# 08-_MCU_PORTE_F_G.net
KiCad netlist of a schematic drawn in Altium Designer
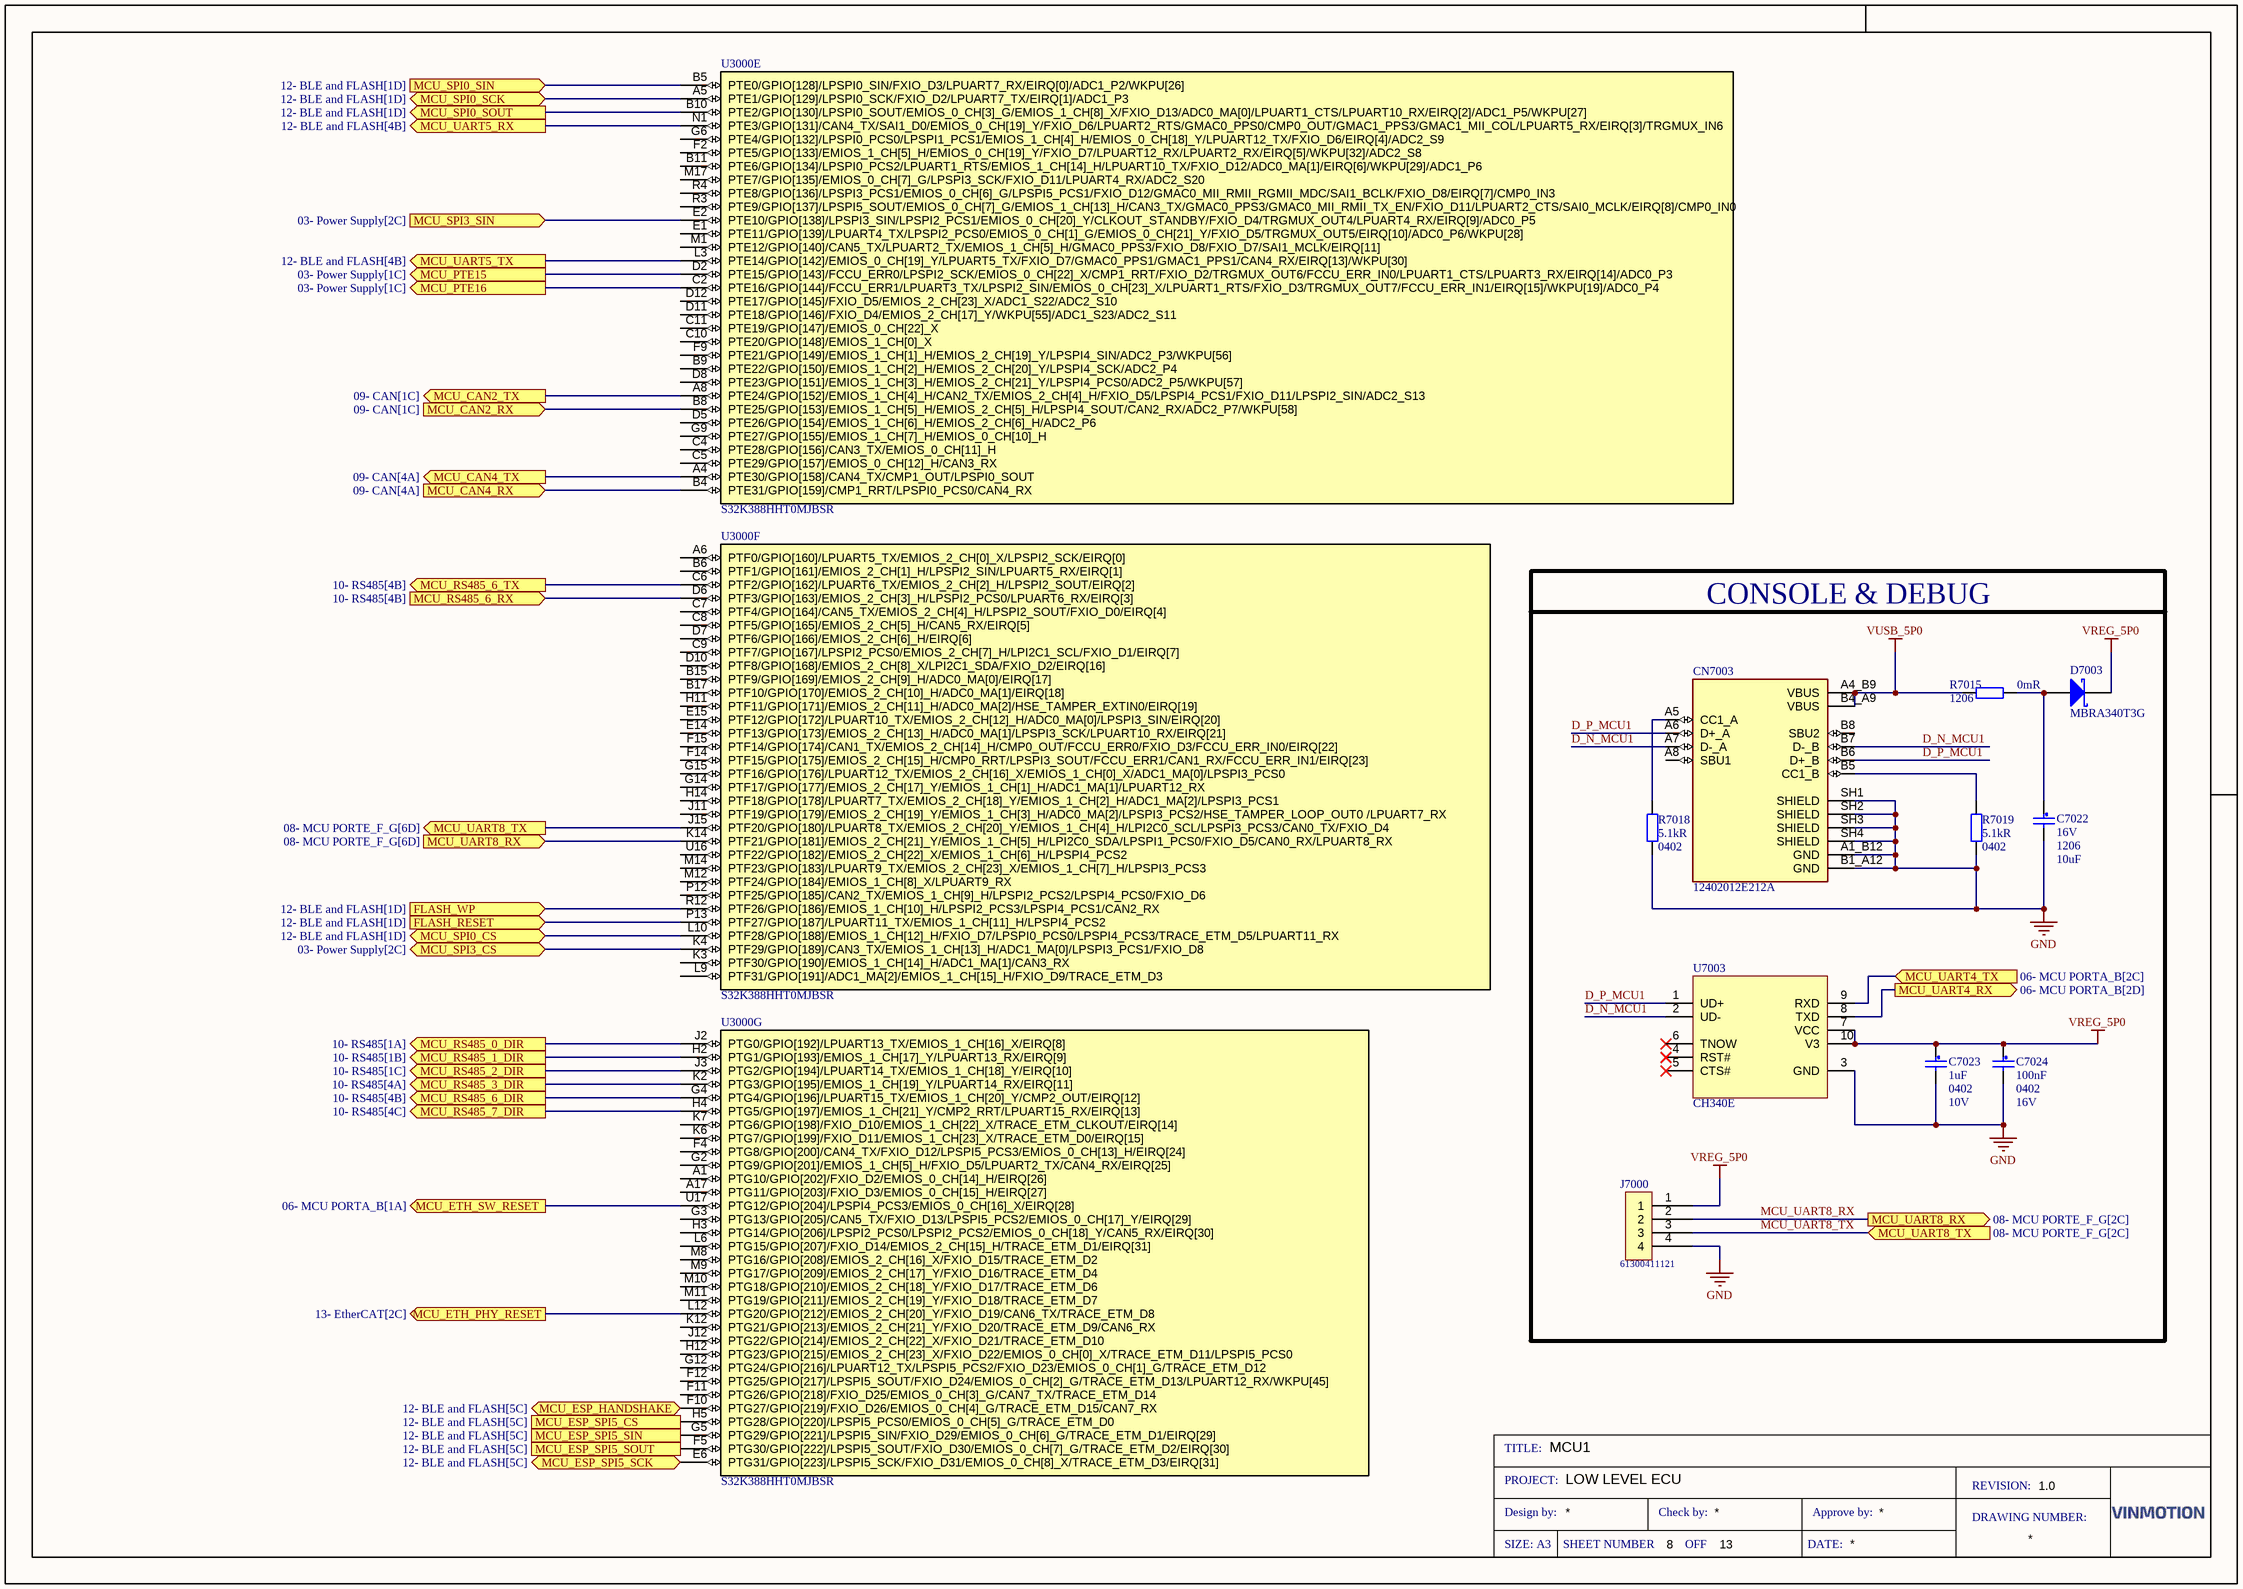
[diagram p0: 08- MCU PORTE_F_G.SchDoc]

(export (version "E")
  (design (tool "Eeschema 10.0.6"))
  (components
    (comp (ref "C7022")
      (value "CL31B106KOHVPNE")
      (footprint "CAP1206")
      (description "CAP CER 10uF 16V 10% X7R 1206 SMD")
      (fields
        (field (name "TOLERANCE") "10%")
        (field (name "VOLTAGE RATING") "16V")
        (field (name "CASE/PACKAGE") "1206")
        (field (name "CAPACITANCE") "10uF")
      )
      (libsource (lib "VMO_Lib") (part "CMP-00045-5"))
    )
    (comp (ref "C7023")
      (value "1uF")
      (footprint "CAP0402")
      (description "CAP CER 1UF 10V X6S 0402")
      (fields
        (field (name "MANUFACTURER") "Samsung")
        (field (name "MANUFACTURER PART NUMBER") "CL05X105KP5NNNC")
        (field (name "CASE/PACKAGE") "0402")
        (field (name "RATED DC VOLTAGE (URDC)") "10V")
      )
      (libsource (lib "VMO_Lib") (part "CMP-01106-1"))
    )
    (comp (ref "C7024")
      (value "0402YC104KAT2A")
      (footprint "CAP0402")
      (description "CAP CER 0.1UF 16V X7R 0402")
      (fields
        (field (name "CAPACITANCE") "100nF")
        (field (name "CASE/PACKAGE") "0402")
        (field (name "VOLTAGE RATING (DC)") "16V")
      )
      (libsource (lib "VMO_Lib") (part "CMP-00988-1"))
    )
    (comp (ref "CN7003")
      (value "12402012E212A")
      (footprint "USB_TYPE_C")
      (description "CONN RCP USB2.0 TYP C 24P SMD RA")
      (fields (field (name "MANUFACTURER") "Amphenol"))
      (libsource (lib "VMO_Lib") (part "CMP-01116-1"))
    )
    (comp (ref "D7003")
      (value "MBRA340T3G")
      (footprint "ON_SMA_NRVBA340T3G_N")
      (description "DIODE SCHOTTKY 40V 3A SMA")
      (fields (field (name "MANUFACTURER") "onsemi"))
      (libsource (lib "VMO_Lib") (part "CMP-00015-4"))
    )
    (comp (ref "J7000")
      (value "61300411121")
      (footprint "WURTH_61300411121_R")
      (description "CONN HEADER VERT 4POS 2.54MM")
      (libsource (lib "VMO_Lib") (part "CMP-00025-12"))
    )
    (comp (ref "R7015")
      (value "AC1206JR-070RL")
      (footprint "RES1206")
      (description "RES 0R 1/4W 5% 1206 SMD")
      (fields
        (field (name "TOLERANCE") "5%")
        (field (name "RESISTANCE") "0mR")
        (field (name "CASE/PACKAGE") "1206")
      )
      (libsource (lib "VMO_Lib") (part "CMP-00083-6"))
    )
    (comp (ref "R7018")
      (value "MCR01MZPF5101")
      (footprint "RES0402")
      (description "RES SMD 5.1K OHM 1% 1/16W 0402")
      (fields
        (field (name "TOLERANCE") "1%")
        (field (name "RESISTANCE") "5.1kR")
        (field (name "CASE/PACKAGE") "0402")
      )
      (libsource (lib "VMO_Lib") (part "CMP-00289-1"))
    )
    (comp (ref "R7019")
      (value "MCR01MZPF5101")
      (footprint "RES0402")
      (description "RES SMD 5.1K OHM 1% 1/16W 0402")
      (fields
        (field (name "TOLERANCE") "1%")
        (field (name "RESISTANCE") "5.1kR")
        (field (name "CASE/PACKAGE") "0402")
      )
      (libsource (lib "VMO_Lib") (part "CMP-00289-1"))
    )
    (comp (ref "U3000")
      (value "S32K388HHT0MJBSR")
      (footprint "BGA289C80P17X17_1400X1400X152")
      (fields (field (name "MANUFACTURER") "NXP Semiconductors"))
      (libsource (lib "VMO_Lib") (part "CMP-01150-1"))
    )
    (comp (ref "U7003")
      (value "CH340E")
      (footprint "CH340E")
      (description "USB TO UART IC")
      (libsource (lib "VMO_Lib") (part "CMP-01117-1"))
    )
  )
  (nets
    (net (code "1") (name "/D_N_MCU1") (class "Default")
      (node (ref "CN7003") (pin "A7") (pinfunction "D-_A_A7") (pintype "bidirectional"))
      (node (ref "CN7003") (pin "B7") (pinfunction "D-_B_B7") (pintype "bidirectional"))
      (node (ref "U7003") (pin "2") (pinfunction "UD-_2") (pintype "passive"))
    )
    (net (code "2") (name "/D_P_MCU1") (class "Default")
      (node (ref "CN7003") (pin "A6") (pinfunction "D+_A_A6") (pintype "bidirectional"))
      (node (ref "CN7003") (pin "B6") (pinfunction "D+_B_B6") (pintype "bidirectional"))
      (node (ref "U7003") (pin "1") (pinfunction "UD+_1") (pintype "passive"))
    )
    (net (code "3") (name "/FLASH_RESET") (class "Default")
      (node (ref "U3000") (pin "P13") (pinfunction "PTF27/GPIO[187]/LPUART11_TX/EMIOS_1_CH[11]_H/LPSPI4_PCS2_P13") (pintype "bidirectional"))
    )
    (net (code "4") (name "/FLASH_WP") (class "Default")
      (node (ref "U3000") (pin "R12") (pinfunction "PTF26/GPIO[186]/EMIOS_1_CH[10]_H/LPSPI2_PCS3/LPSPI4_PCS1/CAN2_RX_R12") (pintype "bidirectional"))
    )
    (net (code "5") (name "/MCU_CAN2_RX") (class "Default")
      (node (ref "U3000") (pin "B8") (pinfunction "PTE25/GPIO[153]/EMIOS_1_CH[5]_H/EMIOS_2_CH[5]_H/LPSPI4_SOUT/CAN2_RX/ADC2_P7/WKPU[58]_B8") (pintype "bidirectional"))
    )
    (net (code "6") (name "/MCU_CAN2_TX") (class "Default")
      (node (ref "U3000") (pin "A8") (pinfunction "PTE24/GPIO[152]/EMIOS_1_CH[4]_H/CAN2_TX/EMIOS_2_CH[4]_H/FXIO_D5/LPSPI4_PCS1/FXIO_D11/LPSPI2_SIN/ADC2_S13_A8") (pintype "bidirectional"))
    )
    (net (code "7") (name "/MCU_CAN4_RX") (class "Default")
      (node (ref "U3000") (pin "B4") (pinfunction "PTE31/GPIO[159]/CMP1_RRT/LPSPI0_PCS0/CAN4_RX_B4") (pintype "bidirectional"))
    )
    (net (code "8") (name "/MCU_CAN4_TX") (class "Default")
      (node (ref "U3000") (pin "A4") (pinfunction "PTE30/GPIO[158]/CAN4_TX/CMP1_OUT/LPSPI0_SOUT_A4") (pintype "bidirectional"))
    )
    (net (code "9") (name "/MCU_ESP_HANDSHAKE") (class "Default")
      (node (ref "U3000") (pin "F10") (pinfunction "PTG27/GPIO[219]/FXIO_D26/EMIOS_0_CH[4]_G/TRACE_ETM_D15/CAN7_RX_F10") (pintype "bidirectional"))
    )
    (net (code "10") (name "/MCU_ESP_SPI5_CS") (class "Default")
      (node (ref "U3000") (pin "H5") (pinfunction "PTG28/GPIO[220]/LPSPI5_PCS0/EMIOS_0_CH[5]_G/TRACE_ETM_D0_H5") (pintype "bidirectional"))
    )
    (net (code "11") (name "/MCU_ESP_SPI5_SCK") (class "Default")
      (node (ref "U3000") (pin "E6") (pinfunction "PTG31/GPIO[223]/LPSPI5_SCK/FXIO_D31/EMIOS_0_CH[8]_X/TRACE_ETM_D3/EIRQ[31]_E6") (pintype "bidirectional"))
    )
    (net (code "12") (name "/MCU_ESP_SPI5_SIN") (class "Default")
      (node (ref "U3000") (pin "G5") (pinfunction "PTG29/GPIO[221]/LPSPI5_SIN/FXIO_D29/EMIOS_0_CH[6]_G/TRACE_ETM_D1/EIRQ[29]_G5") (pintype "bidirectional"))
    )
    (net (code "13") (name "/MCU_ESP_SPI5_SOUT") (class "Default")
      (node (ref "U3000") (pin "F5") (pinfunction "PTG30/GPIO[222]/LPSPI5_SOUT/FXIO_D30/EMIOS_0_CH[7]_G/TRACE_ETM_D2/EIRQ[30]_F5") (pintype "bidirectional"))
    )
    (net (code "14") (name "/MCU_ETH_PHY_RESET") (class "Default")
      (node (ref "U3000") (pin "L12") (pinfunction "PTG20/GPIO[212]/EMIOS_2_CH[20]_Y/FXIO_D19/CAN6_TX/TRACE_ETM_D8_L12") (pintype "bidirectional"))
    )
    (net (code "15") (name "/MCU_ETH_SW_RESET") (class "Default")
      (node (ref "U3000") (pin "U17") (pinfunction "PTG12/GPIO[204]/LPSPI4_PCS3/EMIOS_0_CH[16]_X/EIRQ[28]_U17") (pintype "bidirectional"))
    )
    (net (code "16") (name "/MCU_PTE15") (class "Default")
      (node (ref "U3000") (pin "D2") (pinfunction "PTE15/GPIO[143]/FCCU_ERR0/LPSPI2_SCK/EMIOS_0_CH[22]_X/CMP1_RRT/FXIO_D2/TRGMUX_OUT6/FCCU_ERR_IN0/LPUART1_CTS/LPUART3_RX/EIRQ[14]/ADC0_P3_D2") (pintype "bidirectional"))
    )
    (net (code "17") (name "/MCU_PTE16") (class "Default")
      (node (ref "U3000") (pin "C2") (pinfunction "PTE16/GPIO[144]/FCCU_ERR1/LPUART3_TX/LPSPI2_SIN/EMIOS_0_CH[23]_X/LPUART1_RTS/FXIO_D3/TRGMUX_OUT7/FCCU_ERR_IN1/EIRQ[15]/WKPU[19]/ADC0_P4_C2") (pintype "bidirectional"))
    )
    (net (code "18") (name "/MCU_RS485_0_DIR") (class "Default")
      (node (ref "U3000") (pin "J2") (pinfunction "PTG0/GPIO[192]/LPUART13_TX/EMIOS_1_CH[16]_X/EIRQ[8]_J2") (pintype "bidirectional"))
    )
    (net (code "19") (name "/MCU_RS485_1_DIR") (class "Default")
      (node (ref "U3000") (pin "H2") (pinfunction "PTG1/GPIO[193]/EMIOS_1_CH[17]_Y/LPUART13_RX/EIRQ[9]_H2") (pintype "bidirectional"))
    )
    (net (code "20") (name "/MCU_RS485_2_DIR") (class "Default")
      (node (ref "U3000") (pin "J3") (pinfunction "PTG2/GPIO[194]/LPUART14_TX/EMIOS_1_CH[18]_Y/EIRQ[10]_J3") (pintype "bidirectional"))
    )
    (net (code "21") (name "/MCU_RS485_3_DIR") (class "Default")
      (node (ref "U3000") (pin "K2") (pinfunction "PTG3/GPIO[195]/EMIOS_1_CH[19]_Y/LPUART14_RX/EIRQ[11]_K2") (pintype "bidirectional"))
    )
    (net (code "22") (name "/MCU_RS485_6_DIR") (class "Default")
      (node (ref "U3000") (pin "G4") (pinfunction "PTG4/GPIO[196]/LPUART15_TX/EMIOS_1_CH[20]_Y/CMP2_OUT/EIRQ[12]_G4") (pintype "bidirectional"))
    )
    (net (code "23") (name "/MCU_RS485_6_RX") (class "Default")
      (node (ref "U3000") (pin "D6") (pinfunction "PTF3/GPIO[163]/EMIOS_2_CH[3]_H/LPSPI2_PCS0/LPUART6_RX/EIRQ[3]_D6") (pintype "bidirectional"))
    )
    (net (code "24") (name "/MCU_RS485_6_TX") (class "Default")
      (node (ref "U3000") (pin "C6") (pinfunction "PTF2/GPIO[162]/LPUART6_TX/EMIOS_2_CH[2]_H/LPSPI2_SOUT/EIRQ[2]_C6") (pintype "bidirectional"))
    )
    (net (code "25") (name "/MCU_RS485_7_DIR") (class "Default")
      (node (ref "U3000") (pin "H4") (pinfunction "PTG5/GPIO[197]/EMIOS_1_CH[21]_Y/CMP2_RRT/LPUART15_RX/EIRQ[13]_H4") (pintype "bidirectional"))
    )
    (net (code "26") (name "/MCU_SPI0_CS") (class "Default")
      (node (ref "U3000") (pin "L10") (pinfunction "PTF28/GPIO[188]/EMIOS_1_CH[12]_H/FXIO_D7/LPSPI0_PCS0/LPSPI4_PCS3/TRACE_ETM_D5/LPUART11_RX_L10") (pintype "bidirectional"))
    )
    (net (code "27") (name "/MCU_SPI0_SCK") (class "Default")
      (node (ref "U3000") (pin "A5") (pinfunction "PTE1/GPIO[129]/LPSPI0_SCK/FXIO_D2/LPUART7_TX/EIRQ[1]/ADC1_P3_A5") (pintype "bidirectional"))
    )
    (net (code "28") (name "/MCU_SPI0_SIN") (class "Default")
      (node (ref "U3000") (pin "B5") (pinfunction "PTE0/GPIO[128]/LPSPI0_SIN/FXIO_D3/LPUART7_RX/EIRQ[0]/ADC1_P2/WKPU[26]_B5") (pintype "bidirectional"))
    )
    (net (code "29") (name "/MCU_SPI0_SOUT") (class "Default")
      (node (ref "U3000") (pin "B10") (pinfunction "PTE2/GPIO[130]/LPSPI0_SOUT/EMIOS_0_CH[3]_G/EMIOS_1_CH[8]_X/FXIO_D13/ADC0_MA[0]/LPUART1_CTS/LPUART10_RX/EIRQ[2]/ADC1_P5/WKPU[27]_B10") (pintype "bidirectional"))
    )
    (net (code "30") (name "/MCU_SPI3_CS") (class "Default")
      (node (ref "U3000") (pin "K4") (pinfunction "PTF29/GPIO[189]/CAN3_TX/EMIOS_1_CH[13]_H/ADC1_MA[0]/LPSPI3_PCS1/FXIO_D8_K4") (pintype "bidirectional"))
    )
    (net (code "31") (name "/MCU_SPI3_SIN") (class "Default")
      (node (ref "U3000") (pin "E2") (pinfunction "PTE10/GPIO[138]/LPSPI3_SIN/LPSPI2_PCS1/EMIOS_0_CH[20]_Y/CLKOUT_STANDBY/FXIO_D4/TRGMUX_OUT4/LPUART4_RX/EIRQ[9]/ADC0_P5_E2") (pintype "bidirectional"))
    )
    (net (code "32") (name "/MCU_UART4_RX") (class "Default")
      (node (ref "U7003") (pin "8") (pinfunction "TXD_8") (pintype "passive"))
    )
    (net (code "33") (name "/MCU_UART4_TX") (class "Default")
      (node (ref "U7003") (pin "9") (pinfunction "RXD_9") (pintype "passive"))
    )
    (net (code "34") (name "/MCU_UART5_RX") (class "Default")
      (node (ref "U3000") (pin "N1") (pinfunction "PTE3/GPIO[131]/CAN4_TX/SAI1_D0/EMIOS_0_CH[19]_Y/FXIO_D6/LPUART2_RTS/GMAC0_PPS0/CMP0_OUT/GMAC1_PPS3/GMAC1_MII_COL/LPUART5_RX/EIRQ[3]/TRGMUX_IN6_N1") (pintype "bidirectional"))
    )
    (net (code "35") (name "/MCU_UART5_TX") (class "Default")
      (node (ref "U3000") (pin "L3") (pinfunction "PTE14/GPIO[142]/EMIOS_0_CH[19]_Y/LPUART5_TX/FXIO_D7/GMAC0_PPS1/GMAC1_PPS1/CAN4_RX/EIRQ[13]/WKPU[30]_L3") (pintype "bidirectional"))
    )
    (net (code "36") (name "/MCU_UART8_RX") (class "Default")
      (node (ref "J7000") (pin "2") (pinfunction "2_2") (pintype "passive"))
      (node (ref "U3000") (pin "K14") (pinfunction "PTF21/GPIO[181]/EMIOS_2_CH[21]_Y/EMIOS_1_CH[5]_H/LPI2C0_SDA/LPSPI1_PCS0/FXIO_D5/CAN0_RX/LPUART8_RX_K14") (pintype "bidirectional"))
    )
    (net (code "37") (name "/MCU_UART8_TX") (class "Default")
      (node (ref "J7000") (pin "3") (pinfunction "3_3") (pintype "passive"))
      (node (ref "U3000") (pin "J15") (pinfunction "PTF20/GPIO[180]/LPUART8_TX/EMIOS_2_CH[20]_Y/EMIOS_1_CH[4]_H/LPI2C0_SCL/LPSPI3_PCS3/CAN0_TX/FXIO_D4_J15") (pintype "bidirectional"))
    )
    (net (code "38") (name "GND") (class "Default")
      (node (ref "C7022") (pin "2") (pinfunction "2_2") (pintype "passive"))
      (node (ref "C7023") (pin "2") (pinfunction "2_2") (pintype "passive"))
      (node (ref "C7024") (pin "2") (pinfunction "2_2") (pintype "passive"))
      (node (ref "CN7003") (pin "A1_B12") (pinfunction "GND_A1_B12") (pintype "power_in"))
      (node (ref "CN7003") (pin "B1_A12") (pinfunction "GND_B1_A12") (pintype "power_in"))
      (node (ref "CN7003") (pin "SH1") (pinfunction "SHIELD_SH1") (pintype "passive"))
      (node (ref "CN7003") (pin "SH2") (pinfunction "SHIELD_SH2") (pintype "passive"))
      (node (ref "CN7003") (pin "SH3") (pinfunction "SHIELD_SH3") (pintype "passive"))
      (node (ref "CN7003") (pin "SH4") (pinfunction "SHIELD_SH4") (pintype "passive"))
      (node (ref "J7000") (pin "4") (pinfunction "4_4") (pintype "passive"))
      (node (ref "R7018") (pin "1") (pinfunction "1_1") (pintype "passive"))
      (node (ref "R7019") (pin "1") (pinfunction "1_1") (pintype "passive"))
      (node (ref "U7003") (pin "3") (pinfunction "GND_3") (pintype "passive"))
    )
    (net (code "39") (name "Net-(CN7003-CC1_A)") (class "Default")
      (node (ref "CN7003") (pin "A5") (pinfunction "CC1_A_A5") (pintype "bidirectional"))
      (node (ref "R7018") (pin "2") (pinfunction "2_2") (pintype "passive"))
    )
    (net (code "40") (name "Net-(CN7003-CC1_B)") (class "Default")
      (node (ref "CN7003") (pin "B5") (pinfunction "CC1_B_B5") (pintype "bidirectional"))
      (node (ref "R7019") (pin "2") (pinfunction "2_2") (pintype "passive"))
    )
    (net (code "41") (name "Net-(D7003-A)") (class "Default")
      (node (ref "C7022") (pin "1") (pinfunction "1_1") (pintype "passive"))
      (node (ref "D7003") (pin "2") (pinfunction "A_2") (pintype "passive"))
      (node (ref "R7015") (pin "2") (pinfunction "2_2") (pintype "passive"))
    )
    (net (code "42") (name "VREG_5P0") (class "Default")
      (node (ref "C7023") (pin "1") (pinfunction "1_1") (pintype "passive"))
      (node (ref "C7024") (pin "1") (pinfunction "1_1") (pintype "passive"))
      (node (ref "D7003") (pin "1") (pinfunction "K_1") (pintype "passive"))
      (node (ref "J7000") (pin "1") (pinfunction "1_1") (pintype "passive"))
      (node (ref "U7003") (pin "10") (pinfunction "V3_10") (pintype "passive"))
      (node (ref "U7003") (pin "7") (pinfunction "VCC_7") (pintype "passive"))
    )
    (net (code "43") (name "VUSB_5P0") (class "Default")
      (node (ref "CN7003") (pin "A4_B9") (pinfunction "VBUS_A4_B9") (pintype "power_in"))
      (node (ref "CN7003") (pin "B4_A9") (pinfunction "VBUS_B4_A9") (pintype "power_in"))
      (node (ref "R7015") (pin "1") (pinfunction "1_1") (pintype "passive"))
    )
    (net (code "44") (name "unconnected-(CN7003-SBU1-PadA8)") (class "Default")
      (node (ref "CN7003") (pin "A8") (pinfunction "SBU1_A8") (pintype "bidirectional"))
    )
    (net (code "45") (name "unconnected-(CN7003-SBU2-PadB8)") (class "Default")
      (node (ref "CN7003") (pin "B8") (pinfunction "SBU2_B8") (pintype "bidirectional"))
    )
    (net (code "46") (name "unconnected-(U3000E-PTE4{slash}GPIO[132]{slash}LPSPI0_PCS0{slash}LPSPI1_PCS1{slash}EMIOS_1_CH[4]_H{slash}EMIOS_0_CH[18]_Y{slash}LPUART12_TX{slash}FXIO_D6{slash}EIRQ[4]{slash}ADC2_S9-PadG6)") (class "Default")
      (node (ref "U3000") (pin "G6") (pinfunction "PTE4/GPIO[132]/LPSPI0_PCS0/LPSPI1_PCS1/EMIOS_1_CH[4]_H/EMIOS_0_CH[18]_Y/LPUART12_TX/FXIO_D6/EIRQ[4]/ADC2_S9_G6") (pintype "bidirectional"))
    )
    (net (code "47") (name "unconnected-(U3000E-PTE5{slash}GPIO[133]{slash}EMIOS_1_CH[5]_H{slash}EMIOS_0_CH[19]_Y{slash}FXIO_D7{slash}LPUART12_RX{slash}LPUART2_RX{slash}EIRQ[5]{slash}WKPU[32]{slash}ADC2_S8-PadF2)") (class "Default")
      (node (ref "U3000") (pin "F2") (pinfunction "PTE5/GPIO[133]/EMIOS_1_CH[5]_H/EMIOS_0_CH[19]_Y/FXIO_D7/LPUART12_RX/LPUART2_RX/EIRQ[5]/WKPU[32]/ADC2_S8_F2") (pintype "bidirectional"))
    )
    (net (code "48") (name "unconnected-(U3000E-PTE6{slash}GPIO[134]{slash}LPSPI0_PCS2{slash}LPUART1_RTS{slash}EMIOS_1_CH[14]_H{slash}LPUART10_TX{slash}FXIO_D12{slash}ADC0_MA[1]{slash}EIRQ[6]{slash}WKPU[29]{slash}ADC1_P6-PadB11)") (class "Default")
      (node (ref "U3000") (pin "B11") (pinfunction "PTE6/GPIO[134]/LPSPI0_PCS2/LPUART1_RTS/EMIOS_1_CH[14]_H/LPUART10_TX/FXIO_D12/ADC0_MA[1]/EIRQ[6]/WKPU[29]/ADC1_P6_B11") (pintype "bidirectional"))
    )
    (net (code "49") (name "unconnected-(U3000E-PTE7{slash}GPIO[135]{slash}EMIOS_0_CH[7]_G{slash}LPSPI3_SCK{slash}FXIO_D11{slash}LPUART4_RX{slash}ADC2_S20-PadM17)") (class "Default")
      (node (ref "U3000") (pin "M17") (pinfunction "PTE7/GPIO[135]/EMIOS_0_CH[7]_G/LPSPI3_SCK/FXIO_D11/LPUART4_RX/ADC2_S20_M17") (pintype "bidirectional"))
    )
    (net (code "50") (name "unconnected-(U3000E-PTE8{slash}GPIO[136]{slash}LPSPI3_PCS1{slash}EMIOS_0_CH[6]_G{slash}LPSPI5_PCS1{slash}FXIO_D12{slash}GMAC0_MII_RMII_RGMII_MDC{slash}SAI1_BCLK{slash}FXIO_D8{slash}EIRQ[7]{slash}CMP0_IN3-PadR4)") (class "Default")
      (node (ref "U3000") (pin "R4") (pinfunction "PTE8/GPIO[136]/LPSPI3_PCS1/EMIOS_0_CH[6]_G/LPSPI5_PCS1/FXIO_D12/GMAC0_MII_RMII_RGMII_MDC/SAI1_BCLK/FXIO_D8/EIRQ[7]/CMP0_IN3_R4") (pintype "bidirectional"))
    )
    (net (code "51") (name "unconnected-(U3000E-PTE9{slash}GPIO[137]{slash}LPSPI5_SOUT{slash}EMIOS_0_CH[7]_G{slash}EMIOS_1_CH[13]_H{slash}CAN3_TX{slash}GMAC0_PPS3{slash}GMAC0_MII_RMII_TX_EN{slash}FXIO_D11{slash}LPUART2_CTS{slash}SAI0_MCLK{slash}EIRQ[8]{slash}CMP0_IN0-PadR3)") (class "Default")
      (node (ref "U3000") (pin "R3") (pinfunction "PTE9/GPIO[137]/LPSPI5_SOUT/EMIOS_0_CH[7]_G/EMIOS_1_CH[13]_H/CAN3_TX/GMAC0_PPS3/GMAC0_MII_RMII_TX_EN/FXIO_D11/LPUART2_CTS/SAI0_MCLK/EIRQ[8]/CMP0_IN0_R3") (pintype "bidirectional"))
    )
    (net (code "52") (name "unconnected-(U3000E-PTE11{slash}GPIO[139]{slash}LPUART4_TX{slash}LPSPI2_PCS0{slash}EMIOS_0_CH[1]_G{slash}EMIOS_0_CH[21]_Y{slash}FXIO_D5{slash}TRGMUX_OUT5{slash}EIRQ[10]{slash}ADC0_P6{slash}WKPU[28]-PadE1)") (class "Default")
      (node (ref "U3000") (pin "E1") (pinfunction "PTE11/GPIO[139]/LPUART4_TX/LPSPI2_PCS0/EMIOS_0_CH[1]_G/EMIOS_0_CH[21]_Y/FXIO_D5/TRGMUX_OUT5/EIRQ[10]/ADC0_P6/WKPU[28]_E1") (pintype "bidirectional"))
    )
    (net (code "53") (name "unconnected-(U3000E-PTE12{slash}GPIO[140]{slash}CAN5_TX{slash}LPUART2_TX{slash}EMIOS_1_CH[5]_H{slash}GMAC0_PPS3{slash}FXIO_D8{slash}FXIO_D7{slash}SAI1_MCLK{slash}EIRQ[11]-PadM1)") (class "Default")
      (node (ref "U3000") (pin "M1") (pinfunction "PTE12/GPIO[140]/CAN5_TX/LPUART2_TX/EMIOS_1_CH[5]_H/GMAC0_PPS3/FXIO_D8/FXIO_D7/SAI1_MCLK/EIRQ[11]_M1") (pintype "bidirectional"))
    )
    (net (code "54") (name "unconnected-(U3000E-PTE17{slash}GPIO[145]{slash}FXIO_D5{slash}EMIOS_2_CH[23]_X{slash}ADC1_S22{slash}ADC2_S10-PadD12)") (class "Default")
      (node (ref "U3000") (pin "D12") (pinfunction "PTE17/GPIO[145]/FXIO_D5/EMIOS_2_CH[23]_X/ADC1_S22/ADC2_S10_D12") (pintype "bidirectional"))
    )
    (net (code "55") (name "unconnected-(U3000E-PTE18{slash}GPIO[146]{slash}FXIO_D4{slash}EMIOS_2_CH[17]_Y{slash}WKPU[55]{slash}ADC1_S23{slash}ADC2_S11-PadD11)") (class "Default")
      (node (ref "U3000") (pin "D11") (pinfunction "PTE18/GPIO[146]/FXIO_D4/EMIOS_2_CH[17]_Y/WKPU[55]/ADC1_S23/ADC2_S11_D11") (pintype "bidirectional"))
    )
    (net (code "56") (name "unconnected-(U3000E-PTE19{slash}GPIO[147]{slash}EMIOS_0_CH[22]_X-PadC11)") (class "Default")
      (node (ref "U3000") (pin "C11") (pinfunction "PTE19/GPIO[147]/EMIOS_0_CH[22]_X_C11") (pintype "bidirectional"))
    )
    (net (code "57") (name "unconnected-(U3000E-PTE20{slash}GPIO[148]{slash}EMIOS_1_CH[0]_X-PadC10)") (class "Default")
      (node (ref "U3000") (pin "C10") (pinfunction "PTE20/GPIO[148]/EMIOS_1_CH[0]_X_C10") (pintype "bidirectional"))
    )
    (net (code "58") (name "unconnected-(U3000E-PTE21{slash}GPIO[149]{slash}EMIOS_1_CH[1]_H{slash}EMIOS_2_CH[19]_Y{slash}LPSPI4_SIN{slash}ADC2_P3{slash}WKPU[56]-PadF9)") (class "Default")
      (node (ref "U3000") (pin "F9") (pinfunction "PTE21/GPIO[149]/EMIOS_1_CH[1]_H/EMIOS_2_CH[19]_Y/LPSPI4_SIN/ADC2_P3/WKPU[56]_F9") (pintype "bidirectional"))
    )
    (net (code "59") (name "unconnected-(U3000E-PTE22{slash}GPIO[150]{slash}EMIOS_1_CH[2]_H{slash}EMIOS_2_CH[20]_Y{slash}LPSPI4_SCK{slash}ADC2_P4-PadB9)") (class "Default")
      (node (ref "U3000") (pin "B9") (pinfunction "PTE22/GPIO[150]/EMIOS_1_CH[2]_H/EMIOS_2_CH[20]_Y/LPSPI4_SCK/ADC2_P4_B9") (pintype "bidirectional"))
    )
    (net (code "60") (name "unconnected-(U3000E-PTE23{slash}GPIO[151]{slash}EMIOS_1_CH[3]_H{slash}EMIOS_2_CH[21]_Y{slash}LPSPI4_PCS0{slash}ADC2_P5{slash}WKPU[57]-PadD8)") (class "Default")
      (node (ref "U3000") (pin "D8") (pinfunction "PTE23/GPIO[151]/EMIOS_1_CH[3]_H/EMIOS_2_CH[21]_Y/LPSPI4_PCS0/ADC2_P5/WKPU[57]_D8") (pintype "bidirectional"))
    )
    (net (code "61") (name "unconnected-(U3000E-PTE26{slash}GPIO[154]{slash}EMIOS_1_CH[6]_H{slash}EMIOS_2_CH[6]_H{slash}ADC2_P6-PadD5)") (class "Default")
      (node (ref "U3000") (pin "D5") (pinfunction "PTE26/GPIO[154]/EMIOS_1_CH[6]_H/EMIOS_2_CH[6]_H/ADC2_P6_D5") (pintype "bidirectional"))
    )
    (net (code "62") (name "unconnected-(U3000E-PTE27{slash}GPIO[155]{slash}EMIOS_1_CH[7]_H{slash}EMIOS_0_CH[10]_H-PadG9)") (class "Default")
      (node (ref "U3000") (pin "G9") (pinfunction "PTE27/GPIO[155]/EMIOS_1_CH[7]_H/EMIOS_0_CH[10]_H_G9") (pintype "bidirectional"))
    )
    (net (code "63") (name "unconnected-(U3000E-PTE28{slash}GPIO[156]{slash}CAN3_TX{slash}EMIOS_0_CH[11]_H-PadC4)") (class "Default")
      (node (ref "U3000") (pin "C4") (pinfunction "PTE28/GPIO[156]/CAN3_TX/EMIOS_0_CH[11]_H_C4") (pintype "bidirectional"))
    )
    (net (code "64") (name "unconnected-(U3000E-PTE29{slash}GPIO[157]{slash}EMIOS_0_CH[12]_H{slash}CAN3_RX-PadC5)") (class "Default")
      (node (ref "U3000") (pin "C5") (pinfunction "PTE29/GPIO[157]/EMIOS_0_CH[12]_H/CAN3_RX_C5") (pintype "bidirectional"))
    )
    (net (code "65") (name "unconnected-(U3000F-PTF0{slash}GPIO[160]{slash}LPUART5_TX{slash}EMIOS_2_CH[0]_X{slash}LPSPI2_SCK{slash}EIRQ[0]-PadA6)") (class "Default")
      (node (ref "U3000") (pin "A6") (pinfunction "PTF0/GPIO[160]/LPUART5_TX/EMIOS_2_CH[0]_X/LPSPI2_SCK/EIRQ[0]_A6") (pintype "bidirectional"))
    )
    (net (code "66") (name "unconnected-(U3000F-PTF1{slash}GPIO[161]{slash}EMIOS_2_CH[1]_H{slash}LPSPI2_SIN{slash}LPUART5_RX{slash}EIRQ[1]-PadB6)") (class "Default")
      (node (ref "U3000") (pin "B6") (pinfunction "PTF1/GPIO[161]/EMIOS_2_CH[1]_H/LPSPI2_SIN/LPUART5_RX/EIRQ[1]_B6") (pintype "bidirectional"))
    )
    (net (code "67") (name "unconnected-(U3000F-PTF4{slash}GPIO[164]{slash}CAN5_TX{slash}EMIOS_2_CH[4]_H{slash}LPSPI2_SOUT{slash}FXIO_D0{slash}EIRQ[4]-PadC7)") (class "Default")
      (node (ref "U3000") (pin "C7") (pinfunction "PTF4/GPIO[164]/CAN5_TX/EMIOS_2_CH[4]_H/LPSPI2_SOUT/FXIO_D0/EIRQ[4]_C7") (pintype "bidirectional"))
    )
    (net (code "68") (name "unconnected-(U3000F-PTF5{slash}GPIO[165]{slash}EMIOS_2_CH[5]_H{slash}CAN5_RX{slash}EIRQ[5]-PadC8)") (class "Default")
      (node (ref "U3000") (pin "C8") (pinfunction "PTF5/GPIO[165]/EMIOS_2_CH[5]_H/CAN5_RX/EIRQ[5]_C8") (pintype "bidirectional"))
    )
    (net (code "69") (name "unconnected-(U3000F-PTF6{slash}GPIO[166]{slash}EMIOS_2_CH[6]_H{slash}EIRQ[6]-PadD7)") (class "Default")
      (node (ref "U3000") (pin "D7") (pinfunction "PTF6/GPIO[166]/EMIOS_2_CH[6]_H/EIRQ[6]_D7") (pintype "bidirectional"))
    )
    (net (code "70") (name "unconnected-(U3000F-PTF7{slash}GPIO[167]{slash}LPSPI2_PCS0{slash}EMIOS_2_CH[7]_H{slash}LPI2C1_SCL{slash}FXIO_D1{slash}EIRQ[7]-PadC9)") (class "Default")
      (node (ref "U3000") (pin "C9") (pinfunction "PTF7/GPIO[167]/LPSPI2_PCS0/EMIOS_2_CH[7]_H/LPI2C1_SCL/FXIO_D1/EIRQ[7]_C9") (pintype "bidirectional"))
    )
    (net (code "71") (name "unconnected-(U3000F-PTF8{slash}GPIO[168]{slash}EMIOS_2_CH[8]_X{slash}LPI2C1_SDA{slash}FXIO_D2{slash}EIRQ[16]-PadD10)") (class "Default")
      (node (ref "U3000") (pin "D10") (pinfunction "PTF8/GPIO[168]/EMIOS_2_CH[8]_X/LPI2C1_SDA/FXIO_D2/EIRQ[16]_D10") (pintype "bidirectional"))
    )
    (net (code "72") (name "unconnected-(U3000F-PTF9{slash}GPIO[169]{slash}EMIOS_2_CH[9]_H{slash}ADC0_MA[0]{slash}EIRQ[17]-PadB15)") (class "Default")
      (node (ref "U3000") (pin "B15") (pinfunction "PTF9/GPIO[169]/EMIOS_2_CH[9]_H/ADC0_MA[0]/EIRQ[17]_B15") (pintype "bidirectional"))
    )
    (net (code "73") (name "unconnected-(U3000F-PTF10{slash}GPIO[170]{slash}EMIOS_2_CH[10]_H{slash}ADC0_MA[1]{slash}EIRQ[18]-PadB17)") (class "Default")
      (node (ref "U3000") (pin "B17") (pinfunction "PTF10/GPIO[170]/EMIOS_2_CH[10]_H/ADC0_MA[1]/EIRQ[18]_B17") (pintype "bidirectional"))
    )
    (net (code "74") (name "unconnected-(U3000F-PTF11{slash}GPIO[171]{slash}EMIOS_2_CH[11]_H{slash}ADC0_MA[2]{slash}HSE_TAMPER_EXTIN0{slash}EIRQ[19]-PadH11)") (class "Default")
      (node (ref "U3000") (pin "H11") (pinfunction "PTF11/GPIO[171]/EMIOS_2_CH[11]_H/ADC0_MA[2]/HSE_TAMPER_EXTIN0/EIRQ[19]_H11") (pintype "bidirectional"))
    )
    (net (code "75") (name "unconnected-(U3000F-PTF12{slash}GPIO[172]{slash}LPUART10_TX{slash}EMIOS_2_CH[12]_H{slash}ADC0_MA[0]{slash}LPSPI3_SIN{slash}EIRQ[20]-PadE15)") (class "Default")
      (node (ref "U3000") (pin "E15") (pinfunction "PTF12/GPIO[172]/LPUART10_TX/EMIOS_2_CH[12]_H/ADC0_MA[0]/LPSPI3_SIN/EIRQ[20]_E15") (pintype "bidirectional"))
    )
    (net (code "76") (name "unconnected-(U3000F-PTF13{slash}GPIO[173]{slash}EMIOS_2_CH[13]_H{slash}ADC0_MA[1]{slash}LPSPI3_SCK{slash}LPUART10_RX{slash}EIRQ[21]-PadE14)") (class "Default")
      (node (ref "U3000") (pin "E14") (pinfunction "PTF13/GPIO[173]/EMIOS_2_CH[13]_H/ADC0_MA[1]/LPSPI3_SCK/LPUART10_RX/EIRQ[21]_E14") (pintype "bidirectional"))
    )
    (net (code "77") (name "unconnected-(U3000F-PTF14{slash}GPIO[174]{slash}CAN1_TX{slash}EMIOS_2_CH[14]_H{slash}CMP0_OUT{slash}FCCU_ERR0{slash}FXIO_D3{slash}FCCU_ERR_IN0{slash}EIRQ[22]-PadF15)") (class "Default")
      (node (ref "U3000") (pin "F15") (pinfunction "PTF14/GPIO[174]/CAN1_TX/EMIOS_2_CH[14]_H/CMP0_OUT/FCCU_ERR0/FXIO_D3/FCCU_ERR_IN0/EIRQ[22]_F15") (pintype "bidirectional"))
    )
    (net (code "78") (name "unconnected-(U3000F-PTF15{slash}GPIO[175]{slash}EMIOS_2_CH[15]_H{slash}CMP0_RRT{slash}LPSPI3_SOUT{slash}FCCU_ERR1{slash}CAN1_RX{slash}FCCU_ERR_IN1{slash}EIRQ[23]-PadF14)") (class "Default")
      (node (ref "U3000") (pin "F14") (pinfunction "PTF15/GPIO[175]/EMIOS_2_CH[15]_H/CMP0_RRT/LPSPI3_SOUT/FCCU_ERR1/CAN1_RX/FCCU_ERR_IN1/EIRQ[23]_F14") (pintype "bidirectional"))
    )
    (net (code "79") (name "unconnected-(U3000F-PTF16{slash}GPIO[176]{slash}LPUART12_TX{slash}EMIOS_2_CH[16]_X{slash}EMIOS_1_CH[0]_X{slash}ADC1_MA[0]{slash}LPSPI3_PCS0-PadG15)") (class "Default")
      (node (ref "U3000") (pin "G15") (pinfunction "PTF16/GPIO[176]/LPUART12_TX/EMIOS_2_CH[16]_X/EMIOS_1_CH[0]_X/ADC1_MA[0]/LPSPI3_PCS0_G15") (pintype "bidirectional"))
    )
    (net (code "80") (name "unconnected-(U3000F-PTF17{slash}GPIO[177]{slash}EMIOS_2_CH[17]_Y{slash}EMIOS_1_CH[1]_H{slash}ADC1_MA[1]{slash}LPUART12_RX-PadG14)") (class "Default")
      (node (ref "U3000") (pin "G14") (pinfunction "PTF17/GPIO[177]/EMIOS_2_CH[17]_Y/EMIOS_1_CH[1]_H/ADC1_MA[1]/LPUART12_RX_G14") (pintype "bidirectional"))
    )
    (net (code "81") (name "unconnected-(U3000F-PTF18{slash}GPIO[178]{slash}LPUART7_TX{slash}EMIOS_2_CH[18]_Y{slash}EMIOS_1_CH[2]_H{slash}ADC1_MA[2]{slash}LPSPI3_PCS1-PadH14)") (class "Default")
      (node (ref "U3000") (pin "H14") (pinfunction "PTF18/GPIO[178]/LPUART7_TX/EMIOS_2_CH[18]_Y/EMIOS_1_CH[2]_H/ADC1_MA[2]/LPSPI3_PCS1_H14") (pintype "bidirectional"))
    )
    (net (code "82") (name "unconnected-(U3000F-PTF19{slash}GPIO[179]{slash}EMIOS_2_CH[19]_Y{slash}EMIOS_1_CH[3]_H{slash}ADC0_MA[2]{slash}LPSPI3_PCS2{slash}HSE_TAMPER_LOOP_OUT0_{slash}LPUART7_RX-PadJ11)") (class "Default")
      (node (ref "U3000") (pin "J11") (pinfunction "PTF19/GPIO[179]/EMIOS_2_CH[19]_Y/EMIOS_1_CH[3]_H/ADC0_MA[2]/LPSPI3_PCS2/HSE_TAMPER_LOOP_OUT0_/LPUART7_RX_J11") (pintype "bidirectional"))
    )
    (net (code "83") (name "unconnected-(U3000F-PTF22{slash}GPIO[182]{slash}EMIOS_2_CH[22]_X{slash}EMIOS_1_CH[6]_H{slash}LPSPI4_PCS2-PadU16)") (class "Default")
      (node (ref "U3000") (pin "U16") (pinfunction "PTF22/GPIO[182]/EMIOS_2_CH[22]_X/EMIOS_1_CH[6]_H/LPSPI4_PCS2_U16") (pintype "bidirectional"))
    )
    (net (code "84") (name "unconnected-(U3000F-PTF23{slash}GPIO[183]{slash}LPUART9_TX{slash}EMIOS_2_CH[23]_X{slash}EMIOS_1_CH[7]_H{slash}LPSPI3_PCS3-PadM14)") (class "Default")
      (node (ref "U3000") (pin "M14") (pinfunction "PTF23/GPIO[183]/LPUART9_TX/EMIOS_2_CH[23]_X/EMIOS_1_CH[7]_H/LPSPI3_PCS3_M14") (pintype "bidirectional"))
    )
    (net (code "85") (name "unconnected-(U3000F-PTF24{slash}GPIO[184]{slash}EMIOS_1_CH[8]_X{slash}LPUART9_RX-PadM12)") (class "Default")
      (node (ref "U3000") (pin "M12") (pinfunction "PTF24/GPIO[184]/EMIOS_1_CH[8]_X/LPUART9_RX_M12") (pintype "bidirectional"))
    )
    (net (code "86") (name "unconnected-(U3000F-PTF25{slash}GPIO[185]{slash}CAN2_TX{slash}EMIOS_1_CH[9]_H{slash}LPSPI2_PCS2{slash}LPSPI4_PCS0{slash}FXIO_D6-PadP12)") (class "Default")
      (node (ref "U3000") (pin "P12") (pinfunction "PTF25/GPIO[185]/CAN2_TX/EMIOS_1_CH[9]_H/LPSPI2_PCS2/LPSPI4_PCS0/FXIO_D6_P12") (pintype "bidirectional"))
    )
    (net (code "87") (name "unconnected-(U3000F-PTF30{slash}GPIO[190]{slash}EMIOS_1_CH[14]_H{slash}ADC1_MA[1]{slash}CAN3_RX-PadK3)") (class "Default")
      (node (ref "U3000") (pin "K3") (pinfunction "PTF30/GPIO[190]/EMIOS_1_CH[14]_H/ADC1_MA[1]/CAN3_RX_K3") (pintype "bidirectional"))
    )
    (net (code "88") (name "unconnected-(U3000F-PTF31{slash}GPIO[191]{slash}ADC1_MA[2]{slash}EMIOS_1_CH[15]_H{slash}FXIO_D9{slash}TRACE_ETM_D3-PadL9)") (class "Default")
      (node (ref "U3000") (pin "L9") (pinfunction "PTF31/GPIO[191]/ADC1_MA[2]/EMIOS_1_CH[15]_H/FXIO_D9/TRACE_ETM_D3_L9") (pintype "bidirectional"))
    )
    (net (code "89") (name "unconnected-(U3000G-PTG6{slash}GPIO[198]{slash}FXIO_D10{slash}EMIOS_1_CH[22]_X{slash}TRACE_ETM_CLKOUT{slash}EIRQ[14]-PadK7)") (class "Default")
      (node (ref "U3000") (pin "K7") (pinfunction "PTG6/GPIO[198]/FXIO_D10/EMIOS_1_CH[22]_X/TRACE_ETM_CLKOUT/EIRQ[14]_K7") (pintype "bidirectional"))
    )
    (net (code "90") (name "unconnected-(U3000G-PTG7{slash}GPIO[199]{slash}FXIO_D11{slash}EMIOS_1_CH[23]_X{slash}TRACE_ETM_D0{slash}EIRQ[15]-PadK6)") (class "Default")
      (node (ref "U3000") (pin "K6") (pinfunction "PTG7/GPIO[199]/FXIO_D11/EMIOS_1_CH[23]_X/TRACE_ETM_D0/EIRQ[15]_K6") (pintype "bidirectional"))
    )
    (net (code "91") (name "unconnected-(U3000G-PTG8{slash}GPIO[200]{slash}CAN4_TX{slash}FXIO_D12{slash}LPSPI5_PCS3{slash}EMIOS_0_CH[13]_H{slash}EIRQ[24]-PadF4)") (class "Default")
      (node (ref "U3000") (pin "F4") (pinfunction "PTG8/GPIO[200]/CAN4_TX/FXIO_D12/LPSPI5_PCS3/EMIOS_0_CH[13]_H/EIRQ[24]_F4") (pintype "bidirectional"))
    )
    (net (code "92") (name "unconnected-(U3000G-PTG9{slash}GPIO[201]{slash}EMIOS_1_CH[5]_H{slash}FXIO_D5{slash}LPUART2_TX{slash}CAN4_RX{slash}EIRQ[25]-PadG2)") (class "Default")
      (node (ref "U3000") (pin "G2") (pinfunction "PTG9/GPIO[201]/EMIOS_1_CH[5]_H/FXIO_D5/LPUART2_TX/CAN4_RX/EIRQ[25]_G2") (pintype "bidirectional"))
    )
    (net (code "93") (name "unconnected-(U3000G-PTG10{slash}GPIO[202]{slash}FXIO_D2{slash}EMIOS_0_CH[14]_H{slash}EIRQ[26]-PadA1)") (class "Default")
      (node (ref "U3000") (pin "A1") (pinfunction "PTG10/GPIO[202]/FXIO_D2/EMIOS_0_CH[14]_H/EIRQ[26]_A1") (pintype "bidirectional"))
    )
    (net (code "94") (name "unconnected-(U3000G-PTG11{slash}GPIO[203]{slash}FXIO_D3{slash}EMIOS_0_CH[15]_H{slash}EIRQ[27]-PadA17)") (class "Default")
      (node (ref "U3000") (pin "A17") (pinfunction "PTG11/GPIO[203]/FXIO_D3/EMIOS_0_CH[15]_H/EIRQ[27]_A17") (pintype "bidirectional"))
    )
    (net (code "95") (name "unconnected-(U3000G-PTG13{slash}GPIO[205]{slash}CAN5_TX{slash}FXIO_D13{slash}LPSPI5_PCS2{slash}EMIOS_0_CH[17]_Y{slash}EIRQ[29]-PadG3)") (class "Default")
      (node (ref "U3000") (pin "G3") (pinfunction "PTG13/GPIO[205]/CAN5_TX/FXIO_D13/LPSPI5_PCS2/EMIOS_0_CH[17]_Y/EIRQ[29]_G3") (pintype "bidirectional"))
    )
    (net (code "96") (name "unconnected-(U3000G-PTG14{slash}GPIO[206]{slash}LPSPI2_PCS0{slash}LPSPI2_PCS2{slash}EMIOS_0_CH[18]_Y{slash}CAN5_RX{slash}EIRQ[30]-PadH3)") (class "Default")
      (node (ref "U3000") (pin "H3") (pinfunction "PTG14/GPIO[206]/LPSPI2_PCS0/LPSPI2_PCS2/EMIOS_0_CH[18]_Y/CAN5_RX/EIRQ[30]_H3") (pintype "bidirectional"))
    )
    (net (code "97") (name "unconnected-(U3000G-PTG15{slash}GPIO[207]{slash}FXIO_D14{slash}EMIOS_2_CH[15]_H{slash}TRACE_ETM_D1{slash}EIRQ[31]-PadL6)") (class "Default")
      (node (ref "U3000") (pin "L6") (pinfunction "PTG15/GPIO[207]/FXIO_D14/EMIOS_2_CH[15]_H/TRACE_ETM_D1/EIRQ[31]_L6") (pintype "bidirectional"))
    )
    (net (code "98") (name "unconnected-(U3000G-PTG16{slash}GPIO[208]{slash}EMIOS_2_CH[16]_X{slash}FXIO_D15{slash}TRACE_ETM_D2-PadM8)") (class "Default")
      (node (ref "U3000") (pin "M8") (pinfunction "PTG16/GPIO[208]/EMIOS_2_CH[16]_X/FXIO_D15/TRACE_ETM_D2_M8") (pintype "bidirectional"))
    )
    (net (code "99") (name "unconnected-(U3000G-PTG17{slash}GPIO[209]{slash}EMIOS_2_CH[17]_Y{slash}FXIO_D16{slash}TRACE_ETM_D4-PadM9)") (class "Default")
      (node (ref "U3000") (pin "M9") (pinfunction "PTG17/GPIO[209]/EMIOS_2_CH[17]_Y/FXIO_D16/TRACE_ETM_D4_M9") (pintype "bidirectional"))
    )
    (net (code "100") (name "unconnected-(U3000G-PTG18{slash}GPIO[210]{slash}EMIOS_2_CH[18]_Y{slash}FXIO_D17{slash}TRACE_ETM_D6-PadM10)") (class "Default")
      (node (ref "U3000") (pin "M10") (pinfunction "PTG18/GPIO[210]/EMIOS_2_CH[18]_Y/FXIO_D17/TRACE_ETM_D6_M10") (pintype "bidirectional"))
    )
    (net (code "101") (name "unconnected-(U3000G-PTG19{slash}GPIO[211]{slash}EMIOS_2_CH[19]_Y{slash}FXIO_D18{slash}TRACE_ETM_D7-PadM11)") (class "Default")
      (node (ref "U3000") (pin "M11") (pinfunction "PTG19/GPIO[211]/EMIOS_2_CH[19]_Y/FXIO_D18/TRACE_ETM_D7_M11") (pintype "bidirectional"))
    )
    (net (code "102") (name "unconnected-(U3000G-PTG21{slash}GPIO[213]{slash}EMIOS_2_CH[21]_Y{slash}FXIO_D20{slash}TRACE_ETM_D9{slash}CAN6_RX-PadK12)") (class "Default")
      (node (ref "U3000") (pin "K12") (pinfunction "PTG21/GPIO[213]/EMIOS_2_CH[21]_Y/FXIO_D20/TRACE_ETM_D9/CAN6_RX_K12") (pintype "bidirectional"))
    )
    (net (code "103") (name "unconnected-(U3000G-PTG22{slash}GPIO[214]{slash}EMIOS_2_CH[22]_X{slash}FXIO_D21{slash}TRACE_ETM_D10-PadJ12)") (class "Default")
      (node (ref "U3000") (pin "J12") (pinfunction "PTG22/GPIO[214]/EMIOS_2_CH[22]_X/FXIO_D21/TRACE_ETM_D10_J12") (pintype "bidirectional"))
    )
    (net (code "104") (name "unconnected-(U3000G-PTG23{slash}GPIO[215]{slash}EMIOS_2_CH[23]_X{slash}FXIO_D22{slash}EMIOS_0_CH[0]_X{slash}TRACE_ETM_D11{slash}LPSPI5_PCS0-PadH12)") (class "Default")
      (node (ref "U3000") (pin "H12") (pinfunction "PTG23/GPIO[215]/EMIOS_2_CH[23]_X/FXIO_D22/EMIOS_0_CH[0]_X/TRACE_ETM_D11/LPSPI5_PCS0_H12") (pintype "bidirectional"))
    )
    (net (code "105") (name "unconnected-(U3000G-PTG24{slash}GPIO[216]{slash}LPUART12_TX{slash}LPSPI5_PCS2{slash}FXIO_D23{slash}EMIOS_0_CH[1]_G{slash}TRACE_ETM_D12-PadG12)") (class "Default")
      (node (ref "U3000") (pin "G12") (pinfunction "PTG24/GPIO[216]/LPUART12_TX/LPSPI5_PCS2/FXIO_D23/EMIOS_0_CH[1]_G/TRACE_ETM_D12_G12") (pintype "bidirectional"))
    )
    (net (code "106") (name "unconnected-(U3000G-PTG25{slash}GPIO[217]{slash}LPSPI5_SOUT{slash}FXIO_D24{slash}EMIOS_0_CH[2]_G{slash}TRACE_ETM_D13{slash}LPUART12_RX{slash}WKPU[45]-PadF12)") (class "Default")
      (node (ref "U3000") (pin "F12") (pinfunction "PTG25/GPIO[217]/LPSPI5_SOUT/FXIO_D24/EMIOS_0_CH[2]_G/TRACE_ETM_D13/LPUART12_RX/WKPU[45]_F12") (pintype "bidirectional"))
    )
    (net (code "107") (name "unconnected-(U3000G-PTG26{slash}GPIO[218]{slash}FXIO_D25{slash}EMIOS_0_CH[3]_G{slash}CAN7_TX{slash}TRACE_ETM_D14-PadF11)") (class "Default")
      (node (ref "U3000") (pin "F11") (pinfunction "PTG26/GPIO[218]/FXIO_D25/EMIOS_0_CH[3]_G/CAN7_TX/TRACE_ETM_D14_F11") (pintype "bidirectional"))
    )
    (net (code "108") (name "unconnected-(U7003-CTS#-Pad5)") (class "Default")
      (node (ref "U7003") (pin "5") (pinfunction "CTS#_5") (pintype "passive+no_connect"))
    )
    (net (code "109") (name "unconnected-(U7003-RST#-Pad4)") (class "Default")
      (node (ref "U7003") (pin "4") (pinfunction "RST#_4") (pintype "passive+no_connect"))
    )
    (net (code "110") (name "unconnected-(U7003-TNOW-Pad6)") (class "Default")
      (node (ref "U7003") (pin "6") (pinfunction "TNOW_6") (pintype "passive+no_connect"))
    )
  )
)
